# 2020.net
KiCad netlist of a schematic drawn in Altium Designer
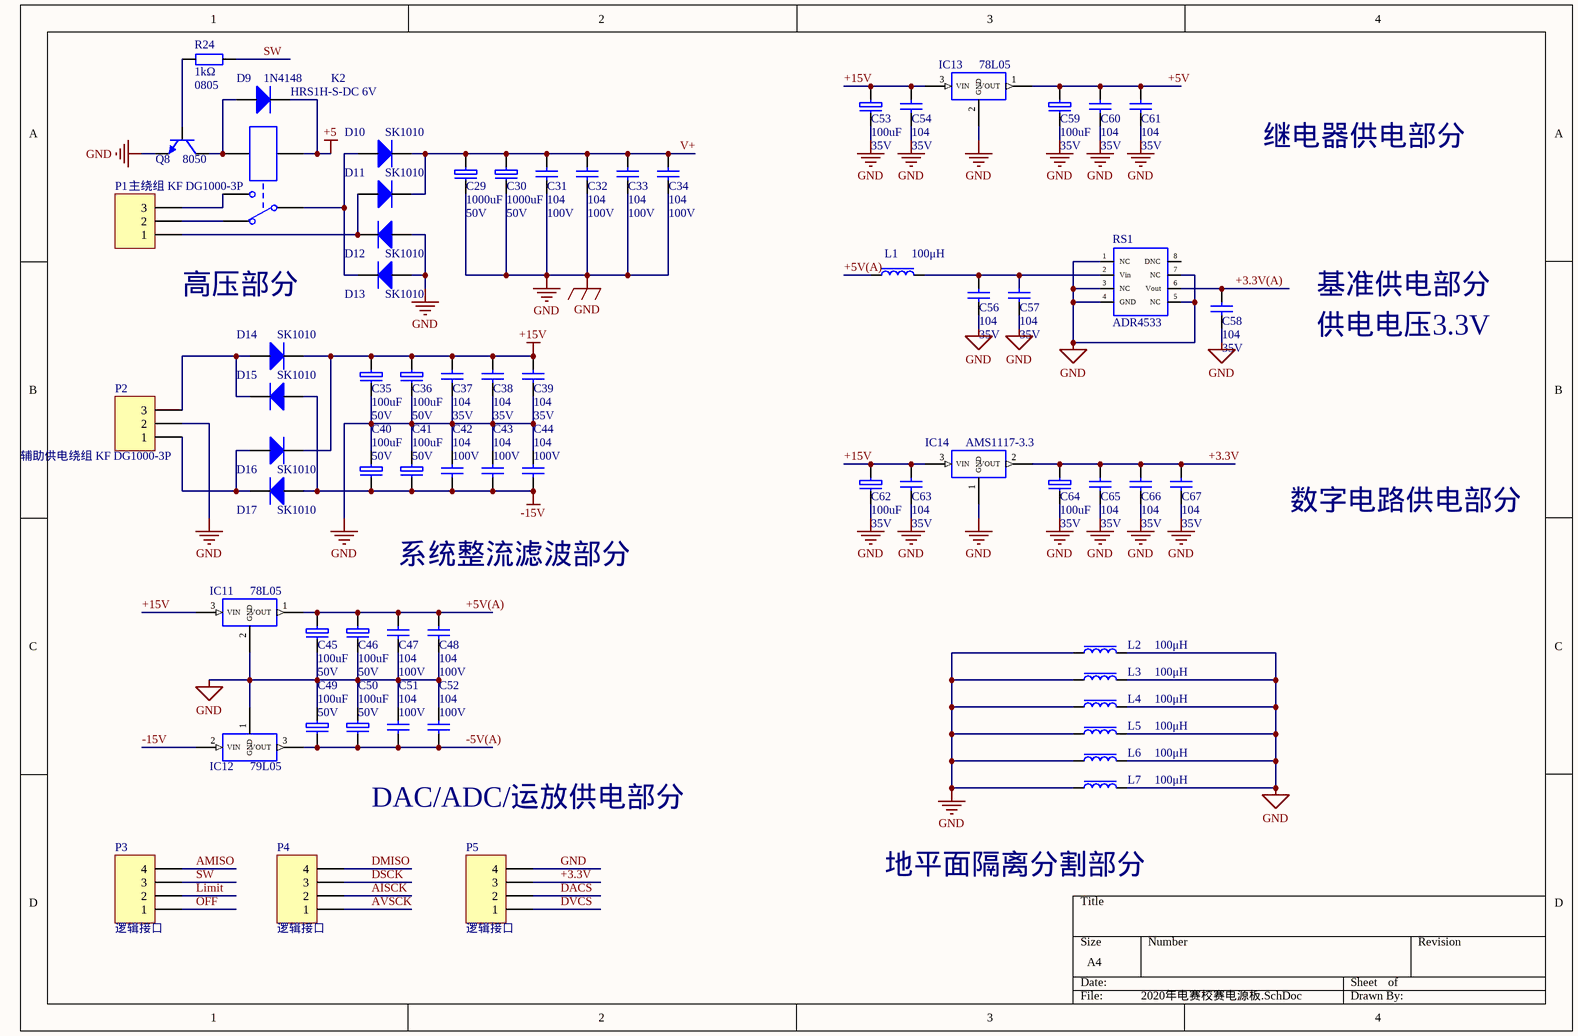
[diagram p0: 2020年电赛校赛电源板.SchDoc]

(export (version "E")
  (design (tool "Eeschema 10.0.6"))
  (components
    (comp (ref "C29")
      (value "1000uF")
      (footprint "CR132(Φ13.2,间距5.1)")
      (description "有极性电容")
      (fields (field (name "ALTIUM_VALUE") "50V"))
      (libsource (lib "原理图库") (part "100uF"))
    )
    (comp (ref "C30")
      (value "1000uF")
      (footprint "CR132(Φ13.2,间距5.1)")
      (description "有极性电容")
      (fields (field (name "ALTIUM_VALUE") "50V"))
      (libsource (lib "原理图库") (part "100uF"))
    )
    (comp (ref "C31")
      (value "104")
      (footprint "C0805")
      (description "无极性电容")
      (fields (field (name "ALTIUM_VALUE") "100V"))
      (libsource (lib "原理图库") (part "104"))
    )
    (comp (ref "C32")
      (value "104")
      (footprint "C0805")
      (description "无极性电容")
      (fields (field (name "ALTIUM_VALUE") "100V"))
      (libsource (lib "原理图库") (part "104"))
    )
    (comp (ref "C33")
      (value "104")
      (footprint "C0805")
      (description "无极性电容")
      (fields (field (name "ALTIUM_VALUE") "100V"))
      (libsource (lib "原理图库") (part "104"))
    )
    (comp (ref "C34")
      (value "104")
      (footprint "C0805")
      (description "无极性电容")
      (fields (field (name "ALTIUM_VALUE") "100V"))
      (libsource (lib "原理图库") (part "104"))
    )
    (comp (ref "C35")
      (value "100uF")
      (footprint "CR100(Φ10.0,间距4.9）")
      (description "有极性电容")
      (fields (field (name "ALTIUM_VALUE") "50V"))
      (libsource (lib "原理图库") (part "100uF"))
    )
    (comp (ref "C36")
      (value "100uF")
      (footprint "CR100(Φ10.0,间距4.9）")
      (description "有极性电容")
      (fields (field (name "ALTIUM_VALUE") "50V"))
      (libsource (lib "原理图库") (part "100uF"))
    )
    (comp (ref "C37")
      (value "104")
      (footprint "C0805")
      (description "无极性电容")
      (fields (field (name "ALTIUM_VALUE") "35V"))
      (libsource (lib "原理图库") (part "104"))
    )
    (comp (ref "C38")
      (value "104")
      (footprint "C0805")
      (description "无极性电容")
      (fields (field (name "ALTIUM_VALUE") "35V"))
      (libsource (lib "原理图库") (part "104"))
    )
    (comp (ref "C39")
      (value "104")
      (footprint "C0805")
      (description "无极性电容")
      (fields (field (name "ALTIUM_VALUE") "35V"))
      (libsource (lib "原理图库") (part "104"))
    )
    (comp (ref "C40")
      (value "100uF")
      (footprint "CR100(Φ10.0,间距4.9）")
      (description "有极性电容")
      (fields (field (name "ALTIUM_VALUE") "50V"))
      (libsource (lib "原理图库") (part "100uF"))
    )
    (comp (ref "C41")
      (value "100uF")
      (footprint "CR100(Φ10.0,间距4.9）")
      (description "有极性电容")
      (fields (field (name "ALTIUM_VALUE") "50V"))
      (libsource (lib "原理图库") (part "100uF"))
    )
    (comp (ref "C42")
      (value "104")
      (footprint "C0805")
      (description "无极性电容")
      (fields (field (name "ALTIUM_VALUE") "100V"))
      (libsource (lib "原理图库") (part "104"))
    )
    (comp (ref "C43")
      (value "104")
      (footprint "C0805")
      (description "无极性电容")
      (fields (field (name "ALTIUM_VALUE") "100V"))
      (libsource (lib "原理图库") (part "104"))
    )
    (comp (ref "C44")
      (value "104")
      (footprint "C0805")
      (description "无极性电容")
      (fields (field (name "ALTIUM_VALUE") "100V"))
      (libsource (lib "原理图库") (part "104"))
    )
    (comp (ref "C45")
      (value "100uF")
      (footprint "CR100(Φ10.0,间距4.9）")
      (description "有极性电容")
      (fields (field (name "ALTIUM_VALUE") "50V"))
      (libsource (lib "原理图库") (part "100uF"))
    )
    (comp (ref "C46")
      (value "100uF")
      (footprint "CR100(Φ10.0,间距4.9）")
      (description "有极性电容")
      (fields (field (name "ALTIUM_VALUE") "50V"))
      (libsource (lib "原理图库") (part "100uF"))
    )
    (comp (ref "C47")
      (value "104")
      (footprint "C0805")
      (description "无极性电容")
      (fields (field (name "ALTIUM_VALUE") "100V"))
      (libsource (lib "原理图库") (part "104"))
    )
    (comp (ref "C48")
      (value "104")
      (footprint "C0805")
      (description "无极性电容")
      (fields (field (name "ALTIUM_VALUE") "100V"))
      (libsource (lib "原理图库") (part "104"))
    )
    (comp (ref "C49")
      (value "100uF")
      (footprint "CR100(Φ10.0,间距4.9）")
      (description "有极性电容")
      (fields (field (name "ALTIUM_VALUE") "50V"))
      (libsource (lib "原理图库") (part "100uF"))
    )
    (comp (ref "C50")
      (value "100uF")
      (footprint "CR100(Φ10.0,间距4.9）")
      (description "有极性电容")
      (fields (field (name "ALTIUM_VALUE") "50V"))
      (libsource (lib "原理图库") (part "100uF"))
    )
    (comp (ref "C51")
      (value "104")
      (footprint "C0805")
      (description "无极性电容")
      (fields (field (name "ALTIUM_VALUE") "100V"))
      (libsource (lib "原理图库") (part "104"))
    )
    (comp (ref "C52")
      (value "104")
      (footprint "C0805")
      (description "无极性电容")
      (fields (field (name "ALTIUM_VALUE") "100V"))
      (libsource (lib "原理图库") (part "104"))
    )
    (comp (ref "C53")
      (value "100uF")
      (footprint "CR100(Φ10.0,间距4.9）")
      (description "有极性电容")
      (fields (field (name "ALTIUM_VALUE") "35V"))
      (libsource (lib "原理图库") (part "100uF"))
    )
    (comp (ref "C54")
      (value "104")
      (footprint "C0805")
      (description "无极性电容")
      (fields (field (name "ALTIUM_VALUE") "35V"))
      (libsource (lib "原理图库") (part "104"))
    )
    (comp (ref "C56")
      (value "104")
      (footprint "C0805")
      (description "无极性电容")
      (fields (field (name "ALTIUM_VALUE") "35V"))
      (libsource (lib "原理图库") (part "104"))
    )
    (comp (ref "C57")
      (value "104")
      (footprint "C0805")
      (description "无极性电容")
      (fields (field (name "ALTIUM_VALUE") "35V"))
      (libsource (lib "原理图库") (part "104"))
    )
    (comp (ref "C58")
      (value "104")
      (footprint "C0805")
      (description "无极性电容")
      (fields (field (name "ALTIUM_VALUE") "35V"))
      (libsource (lib "原理图库") (part "104"))
    )
    (comp (ref "C59")
      (value "100uF")
      (footprint "CT 10*6 - C")
      (description "有极性电容")
      (fields (field (name "ALTIUM_VALUE") "35V"))
      (libsource (lib "原理图库") (part "100uF"))
    )
    (comp (ref "C60")
      (value "104")
      (footprint "C0805")
      (description "无极性电容")
      (fields (field (name "ALTIUM_VALUE") "35V"))
      (libsource (lib "原理图库") (part "104"))
    )
    (comp (ref "C61")
      (value "104")
      (footprint "C0805")
      (description "无极性电容")
      (fields (field (name "ALTIUM_VALUE") "35V"))
      (libsource (lib "原理图库") (part "104"))
    )
    (comp (ref "C62")
      (value "100uF")
      (footprint "CR100(Φ10.0,间距4.9）")
      (description "有极性电容")
      (fields (field (name "ALTIUM_VALUE") "35V"))
      (libsource (lib "原理图库") (part "100uF"))
    )
    (comp (ref "C63")
      (value "104")
      (footprint "C0805")
      (description "无极性电容")
      (fields (field (name "ALTIUM_VALUE") "35V"))
      (libsource (lib "原理图库") (part "104"))
    )
    (comp (ref "C64")
      (value "100uF")
      (footprint "CT 10*6 - C")
      (description "有极性电容")
      (fields (field (name "ALTIUM_VALUE") "35V"))
      (libsource (lib "原理图库") (part "100uF"))
    )
    (comp (ref "C65")
      (value "104")
      (footprint "C0805")
      (description "无极性电容")
      (fields (field (name "ALTIUM_VALUE") "35V"))
      (libsource (lib "原理图库") (part "104"))
    )
    (comp (ref "C66")
      (value "104")
      (footprint "C0805")
      (description "无极性电容")
      (fields (field (name "ALTIUM_VALUE") "35V"))
      (libsource (lib "原理图库") (part "104"))
    )
    (comp (ref "C67")
      (value "104")
      (footprint "C0805")
      (description "无极性电容")
      (fields (field (name "ALTIUM_VALUE") "35V"))
      (libsource (lib "原理图库") (part "104"))
    )
    (comp (ref "D9")
      (value "1N4148")
      (footprint "LL34")
      (description "二极管")
      (libsource (lib "原理图库") (part "Diode"))
    )
    (comp (ref "D10")
      (value "SK1010")
      (footprint "SMC(DO-214AB)")
      (description "二极管")
      (libsource (lib "原理图库") (part "Diode"))
    )
    (comp (ref "D11")
      (value "SK1010")
      (footprint "SMC(DO-214AB)")
      (description "二极管")
      (libsource (lib "原理图库") (part "Diode"))
    )
    (comp (ref "D12")
      (value "SK1010")
      (footprint "SMC(DO-214AB)")
      (description "二极管")
      (libsource (lib "原理图库") (part "Diode"))
    )
    (comp (ref "D13")
      (value "SK1010")
      (footprint "SMC(DO-214AB)")
      (description "二极管")
      (libsource (lib "原理图库") (part "Diode"))
    )
    (comp (ref "D14")
      (value "SK1010")
      (footprint "SMC(DO-214AB)")
      (description "二极管")
      (libsource (lib "原理图库") (part "Diode"))
    )
    (comp (ref "D15")
      (value "SK1010")
      (footprint "SMC(DO-214AB)")
      (description "二极管")
      (libsource (lib "原理图库") (part "Diode"))
    )
    (comp (ref "D16")
      (value "SK1010")
      (footprint "SMC(DO-214AB)")
      (description "二极管")
      (libsource (lib "原理图库") (part "Diode"))
    )
    (comp (ref "D17")
      (value "SK1010")
      (footprint "SMC(DO-214AB)")
      (description "二极管")
      (libsource (lib "原理图库") (part "Diode"))
    )
    (comp (ref "IC11")
      (value "78L05")
      (footprint "SOT-89")
      (description "LDO")
      (libsource (lib "原理图库") (part "AMS1117-3.3"))
    )
    (comp (ref "IC12")
      (value "79L05")
      (footprint "SOT-89")
      (description "LDO")
      (libsource (lib "原理图库") (part "790?"))
    )
    (comp (ref "IC13")
      (value "78L05")
      (footprint "SOT-89")
      (description "LDO")
      (libsource (lib "原理图库") (part "AMS1117-3.3"))
    )
    (comp (ref "IC14")
      (value "AMS1117-3.3")
      (footprint "SOT-89")
      (description "LDO")
      (libsource (lib "") (part "AMS1117-3.3_1"))
    )
    (comp (ref "K2")
      (value "HRS1H-S-DC 6V")
      (footprint "继电器")
      (description "继电器")
      (libsource (lib "原理图库") (part "HRS1H-S-DC 6V"))
    )
    (comp (ref "L1")
      (value "100μH")
      (footprint "R0805")
      (description "电感")
      (libsource (lib "原理图库") (part "470mH"))
    )
    (comp (ref "L2")
      (value "100μH")
      (footprint "R0805")
      (description "电感")
      (libsource (lib "原理图库") (part "470mH"))
    )
    (comp (ref "L3")
      (value "100μH")
      (footprint "R0805")
      (description "电感")
      (libsource (lib "原理图库") (part "470mH"))
    )
    (comp (ref "L4")
      (value "100μH")
      (footprint "R0805")
      (description "电感")
      (libsource (lib "原理图库") (part "470mH"))
    )
    (comp (ref "L5")
      (value "100μH")
      (footprint "R0805")
      (description "电感")
      (libsource (lib "原理图库") (part "470mH"))
    )
    (comp (ref "L6")
      (value "100μH")
      (footprint "R0805")
      (description "电感")
      (libsource (lib "原理图库") (part "470mH"))
    )
    (comp (ref "L7")
      (value "100μH")
      (footprint "R0805")
      (description "电感")
      (libsource (lib "原理图库") (part "470mH"))
    )
    (comp (ref "P1")
      (value "主绕组 KF DG1000-3P")
      (footprint "KF7.62-3P")
      (description "Header, 3-Pin")
      (fields (field (name "PUBLISHER") "Altium Limited"))
      (libsource (lib "Miscellaneous Connectors") (part "Header 3"))
    )
    (comp (ref "P2")
      (value "辅助供电绕组 KF DG1000-3P")
      (footprint "KF7.62-3P")
      (description "Header, 3-Pin")
      (fields (field (name "PUBLISHER") "Altium Limited"))
      (libsource (lib "Miscellaneous Connectors") (part "Header 3"))
    )
    (comp (ref "P3")
      (value "逻辑接口")
      (footprint "XH2.54-4P")
      (description "Header, 4-Pin")
      (fields (field (name "PUBLISHER") "Altium Limited"))
      (libsource (lib "Miscellaneous Connectors") (part "Header 4"))
    )
    (comp (ref "P4")
      (value "逻辑接口")
      (footprint "XH2.54-4P")
      (description "Header, 4-Pin")
      (fields (field (name "PUBLISHER") "Altium Limited"))
      (libsource (lib "Miscellaneous Connectors") (part "Header 4"))
    )
    (comp (ref "P5")
      (value "逻辑接口")
      (footprint "XH2.54-4P")
      (description "Header, 4-Pin")
      (fields (field (name "PUBLISHER") "Altium Limited"))
      (libsource (lib "Miscellaneous Connectors") (part "Header 4"))
    )
    (comp (ref "Q8")
      (value "8050")
      (footprint "SOT-23")
      (description "三极管")
      (libsource (lib "原理图库") (part "NPN"))
    )
    (comp (ref "R24")
      (value "1kΩ")
      (footprint "R0805")
      (description "贴片/直插电阻")
      (fields (field (name "ALTIUM_VALUE") "0805"))
      (libsource (lib "原理图库") (part "10kΩ"))
    )
    (comp (ref "RS1")
      (value "ADR4533")
      (footprint "SOP-8(体宽3.8mm)")
      (description "高精度基准源")
      (libsource (lib "原理图库") (part "ADR4533"))
    )
  )
  (nets
    (net (code "1") (name "+5") (class "Default")
      (node (ref "D9") (pin "2") (pinfunction "K_2") (pintype "passive"))
      (node (ref "K2") (pin "2") (pinfunction "2_2") (pintype "passive"))
    )
    (net (code "2") (name "+15V") (class "Default")
      (node (ref "C35") (pin "1") (pinfunction "+_1") (pintype "passive"))
      (node (ref "C36") (pin "1") (pinfunction "+_1") (pintype "passive"))
      (node (ref "C37") (pin "2") (pintype "passive"))
      (node (ref "C38") (pin "2") (pintype "passive"))
      (node (ref "C39") (pin "2") (pintype "passive"))
      (node (ref "C53") (pin "1") (pinfunction "+_1") (pintype "passive"))
      (node (ref "C54") (pin "2") (pintype "passive"))
      (node (ref "C62") (pin "1") (pinfunction "+_1") (pintype "passive"))
      (node (ref "C63") (pin "2") (pintype "passive"))
      (node (ref "D14") (pin "2") (pinfunction "K_2") (pintype "passive"))
      (node (ref "D16") (pin "2") (pinfunction "K_2") (pintype "passive"))
      (node (ref "IC11") (pin "3") (pinfunction "VIN_3") (pintype "input"))
      (node (ref "IC13") (pin "3") (pinfunction "VIN_3") (pintype "input"))
      (node (ref "IC14") (pin "3") (pinfunction "VIN_3") (pintype "input"))
    )
    (net (code "3") (name "-15V") (class "Default")
      (node (ref "C40") (pin "2") (pinfunction "-_2") (pintype "passive"))
      (node (ref "C41") (pin "2") (pinfunction "-_2") (pintype "passive"))
      (node (ref "C42") (pin "1") (pintype "passive"))
      (node (ref "C43") (pin "1") (pintype "passive"))
      (node (ref "C44") (pin "1") (pintype "passive"))
      (node (ref "D15") (pin "1") (pinfunction "A_1") (pintype "passive"))
      (node (ref "D17") (pin "1") (pinfunction "A_1") (pintype "passive"))
      (node (ref "IC12") (pin "2") (pinfunction "VIN_2") (pintype "input"))
    )
    (net (code "4") (name "/+3.3V") (class "Default")
      (node (ref "C64") (pin "1") (pinfunction "+_1") (pintype "passive"))
      (node (ref "C65") (pin "2") (pintype "passive"))
      (node (ref "C66") (pin "2") (pintype "passive"))
      (node (ref "C67") (pin "2") (pintype "passive"))
      (node (ref "IC14") (pin "2") (pinfunction "VOUT_2") (pintype "output"))
      (node (ref "P5") (pin "3") (pinfunction "3_3") (pintype "passive"))
    )
    (net (code "5") (name "/+3.3V(A)") (class "Default")
      (node (ref "C58") (pin "2") (pintype "passive"))
      (node (ref "RS1") (pin "6") (pinfunction "Vout_6") (pintype "passive"))
    )
    (net (code "6") (name "/+5V") (class "Default")
      (node (ref "C59") (pin "1") (pinfunction "+_1") (pintype "passive"))
      (node (ref "C60") (pin "2") (pintype "passive"))
      (node (ref "C61") (pin "2") (pintype "passive"))
      (node (ref "IC13") (pin "1") (pinfunction "VOUT_1") (pintype "output"))
    )
    (net (code "7") (name "/+5V(A)") (class "Default")
      (node (ref "C45") (pin "1") (pinfunction "+_1") (pintype "passive"))
      (node (ref "C46") (pin "1") (pinfunction "+_1") (pintype "passive"))
      (node (ref "C47") (pin "2") (pintype "passive"))
      (node (ref "C48") (pin "2") (pintype "passive"))
      (node (ref "IC11") (pin "1") (pinfunction "VOUT_1") (pintype "output"))
      (node (ref "L1") (pin "2") (pintype "passive"))
    )
    (net (code "8") (name "/-5V(A)") (class "Default")
      (node (ref "C49") (pin "2") (pinfunction "-_2") (pintype "passive"))
      (node (ref "C50") (pin "2") (pinfunction "-_2") (pintype "passive"))
      (node (ref "C51") (pin "1") (pintype "passive"))
      (node (ref "C52") (pin "1") (pintype "passive"))
      (node (ref "IC12") (pin "3") (pinfunction "VOUT_3") (pintype "output"))
    )
    (net (code "9") (name "/AISCK") (class "Default")
      (node (ref "P4") (pin "2") (pinfunction "2_2") (pintype "passive"))
    )
    (net (code "10") (name "/AMISO") (class "Default")
      (node (ref "P3") (pin "4") (pinfunction "4_4") (pintype "passive"))
    )
    (net (code "11") (name "/AVSCK") (class "Default")
      (node (ref "P4") (pin "1") (pinfunction "1_1") (pintype "passive"))
    )
    (net (code "12") (name "/DACS") (class "Default")
      (node (ref "P5") (pin "2") (pinfunction "2_2") (pintype "passive"))
    )
    (net (code "13") (name "/DMISO") (class "Default")
      (node (ref "P4") (pin "4") (pinfunction "4_4") (pintype "passive"))
    )
    (net (code "14") (name "/DSCK") (class "Default")
      (node (ref "P4") (pin "3") (pinfunction "3_3") (pintype "passive"))
    )
    (net (code "15") (name "/DVCS") (class "Default")
      (node (ref "P5") (pin "1") (pinfunction "1_1") (pintype "passive"))
    )
    (net (code "16") (name "/Limit") (class "Default")
      (node (ref "P3") (pin "2") (pinfunction "2_2") (pintype "passive"))
    )
    (net (code "17") (name "/OFF") (class "Default")
      (node (ref "P3") (pin "1") (pinfunction "1_1") (pintype "passive"))
    )
    (net (code "18") (name "/SW") (class "Default")
      (node (ref "P3") (pin "3") (pinfunction "3_3") (pintype "passive"))
      (node (ref "R24") (pin "2") (pintype "passive"))
    )
    (net (code "19") (name "/V+") (class "Default")
      (node (ref "C29") (pin "1") (pinfunction "+_1") (pintype "passive"))
      (node (ref "C30") (pin "1") (pinfunction "+_1") (pintype "passive"))
      (node (ref "C31") (pin "2") (pintype "passive"))
      (node (ref "C32") (pin "2") (pintype "passive"))
      (node (ref "C33") (pin "2") (pintype "passive"))
      (node (ref "C34") (pin "2") (pintype "passive"))
      (node (ref "D10") (pin "2") (pinfunction "K_2") (pintype "passive"))
      (node (ref "D11") (pin "2") (pinfunction "K_2") (pintype "passive"))
    )
    (net (code "20") (name "GND") (class "Default")
      (node (ref "C29") (pin "2") (pinfunction "-_2") (pintype "passive"))
      (node (ref "C30") (pin "2") (pinfunction "-_2") (pintype "passive"))
      (node (ref "C31") (pin "1") (pintype "passive"))
      (node (ref "C32") (pin "1") (pintype "passive"))
      (node (ref "C33") (pin "1") (pintype "passive"))
      (node (ref "C34") (pin "1") (pintype "passive"))
      (node (ref "C35") (pin "2") (pinfunction "-_2") (pintype "passive"))
      (node (ref "C36") (pin "2") (pinfunction "-_2") (pintype "passive"))
      (node (ref "C37") (pin "1") (pintype "passive"))
      (node (ref "C38") (pin "1") (pintype "passive"))
      (node (ref "C39") (pin "1") (pintype "passive"))
      (node (ref "C40") (pin "1") (pinfunction "+_1") (pintype "passive"))
      (node (ref "C41") (pin "1") (pinfunction "+_1") (pintype "passive"))
      (node (ref "C42") (pin "2") (pintype "passive"))
      (node (ref "C43") (pin "2") (pintype "passive"))
      (node (ref "C44") (pin "2") (pintype "passive"))
      (node (ref "C45") (pin "2") (pinfunction "-_2") (pintype "passive"))
      (node (ref "C46") (pin "2") (pinfunction "-_2") (pintype "passive"))
      (node (ref "C47") (pin "1") (pintype "passive"))
      (node (ref "C48") (pin "1") (pintype "passive"))
      (node (ref "C49") (pin "1") (pinfunction "+_1") (pintype "passive"))
      (node (ref "C50") (pin "1") (pinfunction "+_1") (pintype "passive"))
      (node (ref "C51") (pin "2") (pintype "passive"))
      (node (ref "C52") (pin "2") (pintype "passive"))
      (node (ref "C53") (pin "2") (pinfunction "-_2") (pintype "passive"))
      (node (ref "C54") (pin "1") (pintype "passive"))
      (node (ref "C56") (pin "1") (pintype "passive"))
      (node (ref "C57") (pin "1") (pintype "passive"))
      (node (ref "C58") (pin "1") (pintype "passive"))
      (node (ref "C59") (pin "2") (pinfunction "-_2") (pintype "passive"))
      (node (ref "C60") (pin "1") (pintype "passive"))
      (node (ref "C61") (pin "1") (pintype "passive"))
      (node (ref "C62") (pin "2") (pinfunction "-_2") (pintype "passive"))
      (node (ref "C63") (pin "1") (pintype "passive"))
      (node (ref "C64") (pin "2") (pinfunction "-_2") (pintype "passive"))
      (node (ref "C65") (pin "1") (pintype "passive"))
      (node (ref "C66") (pin "1") (pintype "passive"))
      (node (ref "C67") (pin "1") (pintype "passive"))
      (node (ref "D12") (pin "1") (pinfunction "A_1") (pintype "passive"))
      (node (ref "D13") (pin "1") (pinfunction "A_1") (pintype "passive"))
      (node (ref "IC11") (pin "2") (pinfunction "GND_2") (pintype "passive"))
      (node (ref "IC12") (pin "1") (pinfunction "GND_1") (pintype "passive"))
      (node (ref "IC13") (pin "2") (pinfunction "GND_2") (pintype "passive"))
      (node (ref "IC14") (pin "1") (pinfunction "GND_1") (pintype "passive"))
      (node (ref "L2") (pin "1") (pintype "passive"))
      (node (ref "L2") (pin "2") (pintype "passive"))
      (node (ref "L3") (pin "1") (pintype "passive"))
      (node (ref "L3") (pin "2") (pintype "passive"))
      (node (ref "L4") (pin "1") (pintype "passive"))
      (node (ref "L4") (pin "2") (pintype "passive"))
      (node (ref "L5") (pin "1") (pintype "passive"))
      (node (ref "L5") (pin "2") (pintype "passive"))
      (node (ref "L6") (pin "1") (pintype "passive"))
      (node (ref "L6") (pin "2") (pintype "passive"))
      (node (ref "L7") (pin "1") (pintype "passive"))
      (node (ref "L7") (pin "2") (pintype "passive"))
      (node (ref "P2") (pin "2") (pinfunction "2_2") (pintype "passive"))
      (node (ref "P5") (pin "4") (pinfunction "4_4") (pintype "passive"))
      (node (ref "Q8") (pin "3") (pinfunction "E_3") (pintype "passive"))
      (node (ref "RS1") (pin "1") (pinfunction "NC_1") (pintype "passive"))
      (node (ref "RS1") (pin "3") (pinfunction "NC_3") (pintype "passive"))
      (node (ref "RS1") (pin "4") (pinfunction "GND_4") (pintype "passive"))
      (node (ref "RS1") (pin "5") (pinfunction "NC_5") (pintype "passive"))
      (node (ref "RS1") (pin "7") (pinfunction "NC_7") (pintype "passive"))
    )
    (net (code "21") (name "Net-(D9-A)") (class "Default")
      (node (ref "D9") (pin "1") (pinfunction "A_1") (pintype "passive"))
      (node (ref "K2") (pin "5") (pinfunction "5_5") (pintype "passive"))
      (node (ref "Q8") (pin "2") (pinfunction "C_2") (pintype "passive"))
    )
    (net (code "22") (name "Net-(D10-A)") (class "Default")
      (node (ref "D10") (pin "1") (pinfunction "A_1") (pintype "passive"))
      (node (ref "D13") (pin "2") (pinfunction "K_2") (pintype "passive"))
      (node (ref "K2") (pin "4") (pinfunction "4_4") (pintype "passive"))
    )
    (net (code "23") (name "Net-(D11-A)") (class "Default")
      (node (ref "D11") (pin "1") (pinfunction "A_1") (pintype "passive"))
      (node (ref "D12") (pin "2") (pinfunction "K_2") (pintype "passive"))
      (node (ref "P1") (pin "1") (pinfunction "1_1") (pintype "passive"))
    )
    (net (code "24") (name "Net-(D14-A)") (class "Default")
      (node (ref "D14") (pin "1") (pinfunction "A_1") (pintype "passive"))
      (node (ref "D15") (pin "2") (pinfunction "K_2") (pintype "passive"))
      (node (ref "P2") (pin "3") (pinfunction "3_3") (pintype "passive"))
    )
    (net (code "25") (name "Net-(D16-A)") (class "Default")
      (node (ref "D16") (pin "1") (pinfunction "A_1") (pintype "passive"))
      (node (ref "D17") (pin "2") (pinfunction "K_2") (pintype "passive"))
      (node (ref "P2") (pin "1") (pinfunction "1_1") (pintype "passive"))
    )
    (net (code "26") (name "Net-(K2-Pad1)") (class "Default")
      (node (ref "K2") (pin "1") (pinfunction "1_1") (pintype "passive"))
      (node (ref "P1") (pin "2") (pinfunction "2_2") (pintype "passive"))
    )
    (net (code "27") (name "Net-(K2-Pad6)") (class "Default")
      (node (ref "K2") (pin "6") (pinfunction "6_6") (pintype "passive"))
      (node (ref "P1") (pin "3") (pinfunction "3_3") (pintype "passive"))
    )
    (net (code "28") (name "Net-(Q8-B)") (class "Default")
      (node (ref "Q8") (pin "1") (pinfunction "B_1") (pintype "passive"))
      (node (ref "R24") (pin "1") (pintype "passive"))
    )
    (net (code "29") (name "Net-(RS1-Vin)") (class "Default")
      (node (ref "C56") (pin "2") (pintype "passive"))
      (node (ref "C57") (pin "2") (pintype "passive"))
      (node (ref "L1") (pin "1") (pintype "passive"))
      (node (ref "RS1") (pin "2") (pinfunction "Vin_2") (pintype "passive"))
    )
    (net (code "30") (name "unconnected-(RS1-DNC-Pad8)") (class "Default")
      (node (ref "RS1") (pin "8") (pinfunction "DNC_8") (pintype "passive"))
    )
  )
)
